# Pyro_Cut-Down.net
KiCad netlist of a schematic drawn in EAGLE
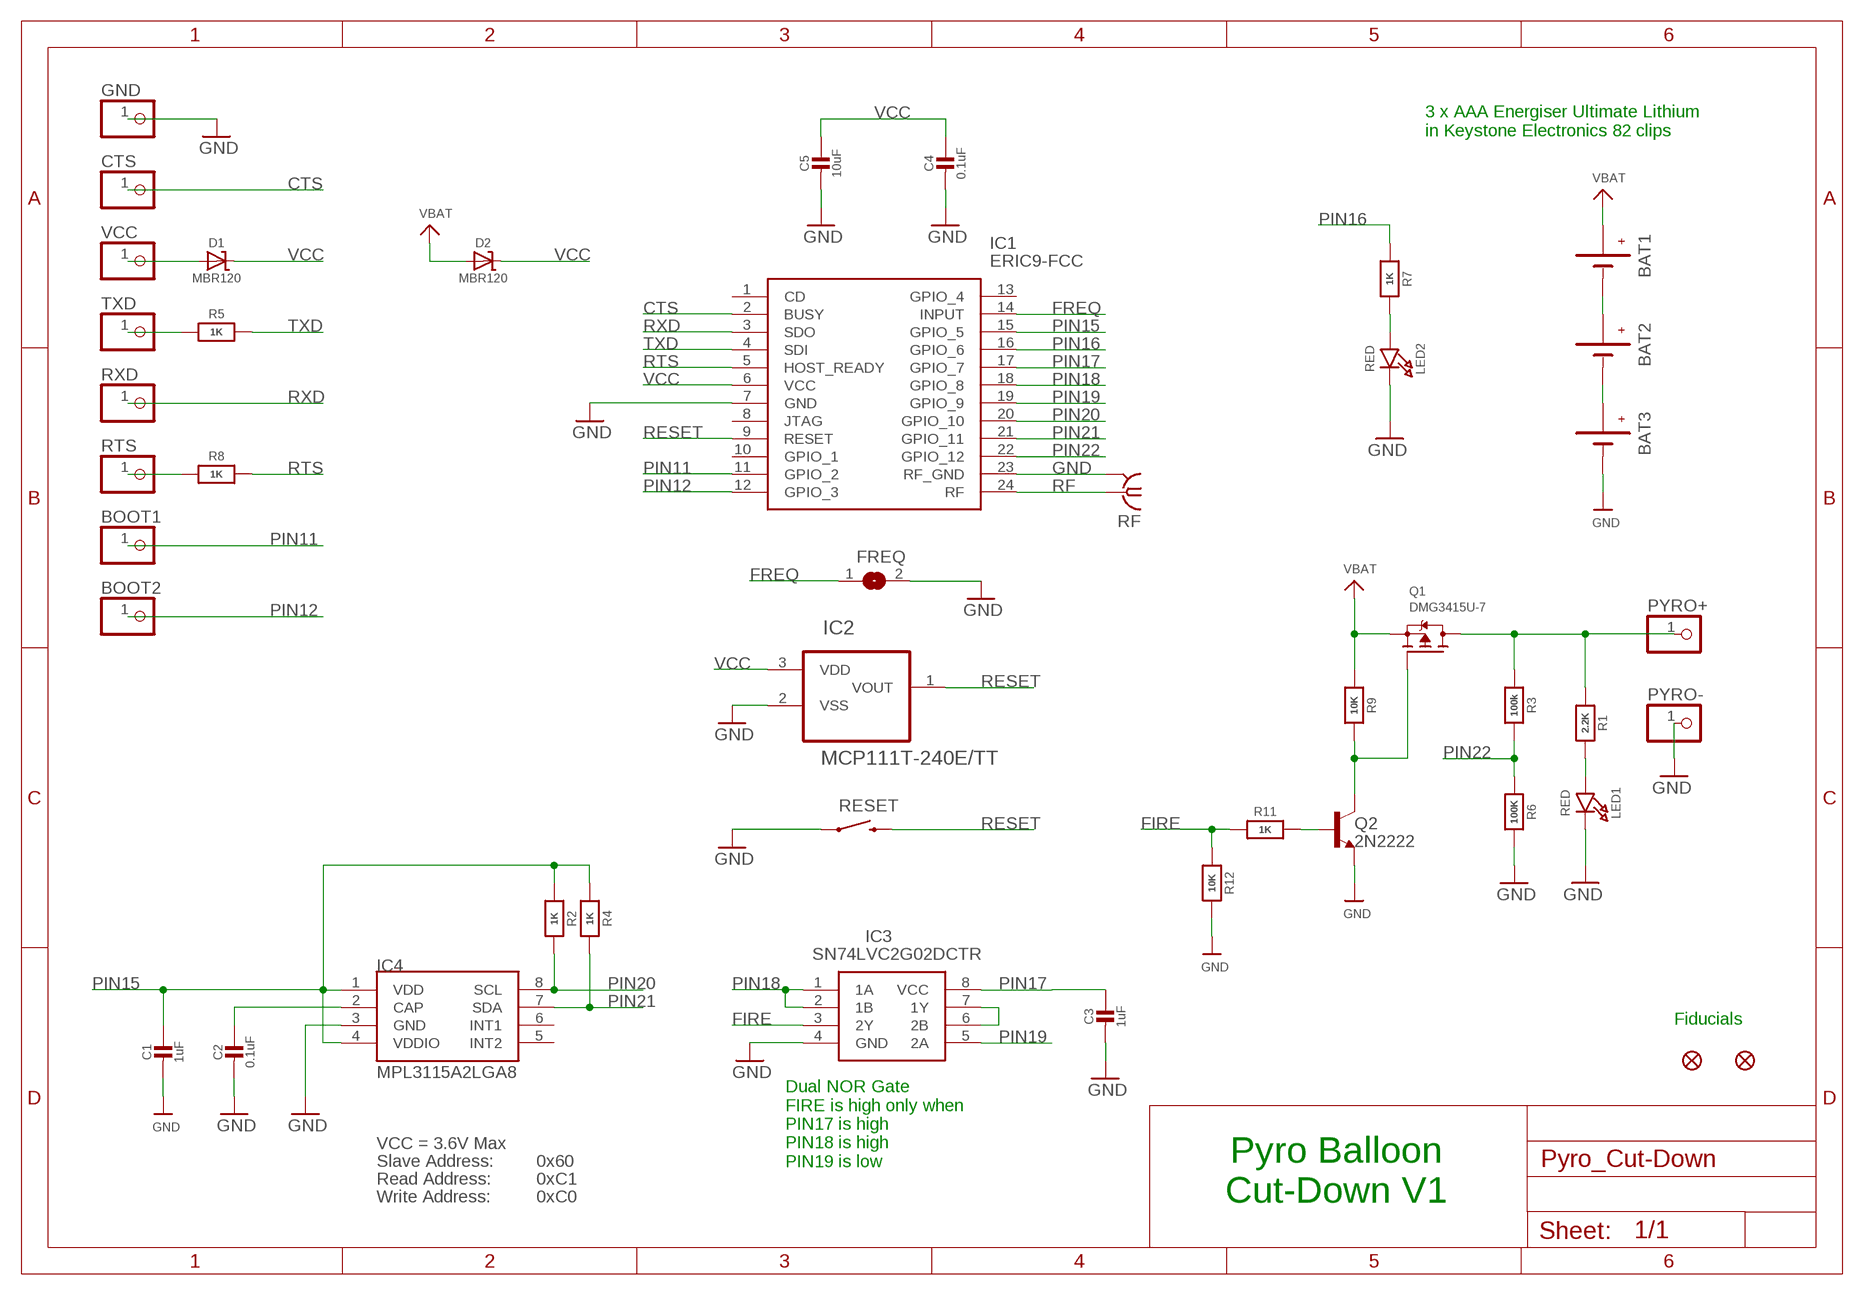
[diagram p0: schematic, sheet 1]

(export (version "E")
  (design (tool "Eeschema 10.0.6"))
  (components
    (comp (ref "BAT1")
      (value "BATTERYKEYSTONE82")
      (footprint "eagle-import:BATTERY-AAA-KEYSTONE82")
      (libsource (lib "eagle-import") (part "BATTERYKEYSTONE82"))
    )
    (comp (ref "BAT2")
      (value "BATTERYKEYSTONE82")
      (footprint "eagle-import:BATTERY-AAA-KEYSTONE82")
      (libsource (lib "eagle-import") (part "BATTERYKEYSTONE82"))
    )
    (comp (ref "BAT3")
      (value "BATTERYKEYSTONE82")
      (footprint "eagle-import:BATTERY-AAA-KEYSTONE82")
      (libsource (lib "eagle-import") (part "BATTERYKEYSTONE82"))
    )
    (comp (ref "BOOT1")
      (value "PINHD-1X1")
      (footprint "eagle-import:1X01")
      (libsource (lib "eagle-import") (part "PINHD-1X1"))
    )
    (comp (ref "BOOT2")
      (value "PINHD-1X1")
      (footprint "eagle-import:1X01")
      (libsource (lib "eagle-import") (part "PINHD-1X1"))
    )
    (comp (ref "C1")
      (value "1uF")
      (footprint "eagle-import:0603-NO")
      (libsource (lib "eagle-import") (part "CAP_CERAMIC0603_NO"))
    )
    (comp (ref "C2")
      (value "0.1uF")
      (footprint "eagle-import:0603-NO")
      (libsource (lib "eagle-import") (part "CAP_CERAMIC0603_NO"))
    )
    (comp (ref "C3")
      (value "1uF")
      (footprint "eagle-import:0603-NO")
      (libsource (lib "eagle-import") (part "CAP_CERAMIC0603_NO"))
    )
    (comp (ref "C4")
      (value "0.1uF")
      (footprint "eagle-import:0603-NO")
      (libsource (lib "eagle-import") (part "CAP_CERAMIC0603_NO"))
    )
    (comp (ref "C5")
      (value "10uF")
      (footprint "eagle-import:0805-NO")
      (libsource (lib "eagle-import") (part "CAP_CERAMIC0805-NOOUTLINE"))
    )
    (comp (ref "CTS")
      (value "PINHD-1X1")
      (footprint "eagle-import:1X01")
      (libsource (lib "eagle-import") (part "PINHD-1X1"))
    )
    (comp (ref "D1")
      (value "MBR120")
      (footprint "eagle-import:SOD-123")
      (libsource (lib "eagle-import") (part "DIODE-SCHOTTKYSOD-123"))
    )
    (comp (ref "D2")
      (value "MBR120")
      (footprint "eagle-import:SOD-123")
      (libsource (lib "eagle-import") (part "DIODE-SCHOTTKYSOD-123"))
    )
    (comp (ref "FD1")
      (value "FIDUCIAL1X2")
      (footprint "eagle-import:FIDUCIAL-1X2")
      (libsource (lib "eagle-import") (part "FIDUCIAL1X2"))
    )
    (comp (ref "FD2")
      (value "FIDUCIAL1X2")
      (footprint "eagle-import:FIDUCIAL-1X2")
      (libsource (lib "eagle-import") (part "FIDUCIAL1X2"))
    )
    (comp (ref "FREQ")
      (value "SOLDERJUMPER")
      (footprint "eagle-import:SOLDERJUMPER_ARROW_NOPASTE")
      (libsource (lib "eagle-import") (part "SOLDERJUMPER"))
    )
    (comp (ref "GND")
      (value "PINHD-1X1")
      (footprint "eagle-import:1X01")
      (libsource (lib "eagle-import") (part "PINHD-1X1"))
    )
    (comp (ref "IC1")
      (value "ERIC9-FCC")
      (footprint "eagle-import:ERIC4")
      (fields (field (name "ARROW_PART_NUMBER") "eRIC9-FCC"))
      (libsource (lib "eagle-import") (part "ERIC9-FCC"))
    )
    (comp (ref "IC2")
      (value "MCP111T-240E/TT")
      (footprint "eagle-import:SOT95P237X112-3N")
      (fields (field (name "MPN") "MCP111T-270E/TT") (field (name "MPN_1") "MCP111T-240E/TT"))
      (libsource (lib "eagle-import") (part "MCP111T-270E/TT"))
    )
    (comp (ref "IC3")
      (value "SN74LVC2G02DCTR")
      (footprint "eagle-import:SOP65P400X130-8N")
      (libsource (lib "eagle-import") (part "SN74LVC2G02DCTR"))
    )
    (comp (ref "IC4")
      (value "MPL3115A2LGA8")
      (footprint "eagle-import:LGA8")
      (libsource (lib "eagle-import") (part "MPL3115A2LGA8"))
    )
    (comp (ref "LED1")
      (value "RED")
      (footprint "eagle-import:CHIPLED_0805_NOOUTLINE")
      (libsource (lib "eagle-import") (part "LED0805_NOOUTLINE"))
    )
    (comp (ref "LED2")
      (value "RED")
      (footprint "eagle-import:CHIPLED_0805_NOOUTLINE")
      (libsource (lib "eagle-import") (part "LED0805_NOOUTLINE"))
    )
    (comp (ref "PYRO+")
      (value "PINHD-1X1")
      (footprint "eagle-import:1X01")
      (libsource (lib "eagle-import") (part "PINHD-1X1"))
    )
    (comp (ref "PYRO-")
      (value "PINHD-1X1")
      (footprint "eagle-import:1X01")
      (libsource (lib "eagle-import") (part "PINHD-1X1"))
    )
    (comp (ref "Q1")
      (value "DMG3415U-7")
      (footprint "eagle-import:SOT23-WIDE")
      (libsource (lib "eagle-import") (part "MOSFET-PWIDE"))
    )
    (comp (ref "Q2")
      (value "2N2222")
      (footprint "eagle-import:SOT23-BEC")
      (libsource (lib "eagle-import") (part "-NPN-SOT23-BECMMBT2222ALT1"))
    )
    (comp (ref "R1")
      (value "2.2K")
      (footprint "eagle-import:0603-NO")
      (libsource (lib "eagle-import") (part "RESISTOR_0603_NOOUT"))
    )
    (comp (ref "R2")
      (value "1K")
      (footprint "eagle-import:0603-NO")
      (libsource (lib "eagle-import") (part "RESISTOR_0603_NOOUT"))
    )
    (comp (ref "R3")
      (value "100k")
      (footprint "eagle-import:0603-NO")
      (libsource (lib "eagle-import") (part "RESISTOR_0603_NOOUT"))
    )
    (comp (ref "R4")
      (value "1K")
      (footprint "eagle-import:0603-NO")
      (libsource (lib "eagle-import") (part "RESISTOR_0603_NOOUT"))
    )
    (comp (ref "R5")
      (value "1K")
      (footprint "eagle-import:0603-NO")
      (libsource (lib "eagle-import") (part "RESISTOR_0603_NOOUT"))
    )
    (comp (ref "R6")
      (value "100K")
      (footprint "eagle-import:0603-NO")
      (libsource (lib "eagle-import") (part "RESISTOR_0603_NOOUT"))
    )
    (comp (ref "R7")
      (value "1K")
      (footprint "eagle-import:0603-NO")
      (libsource (lib "eagle-import") (part "RESISTOR_0603_NOOUT"))
    )
    (comp (ref "R8")
      (value "1K")
      (footprint "eagle-import:0603-NO")
      (libsource (lib "eagle-import") (part "RESISTOR_0603_NOOUT"))
    )
    (comp (ref "R9")
      (value "10K")
      (footprint "eagle-import:0603-NO")
      (libsource (lib "eagle-import") (part "RESISTOR_0603_NOOUT"))
    )
    (comp (ref "R11")
      (value "1K")
      (footprint "eagle-import:0603-NO")
      (libsource (lib "eagle-import") (part "RESISTOR_0603_NOOUT"))
    )
    (comp (ref "R12")
      (value "10K")
      (footprint "eagle-import:0603-NO")
      (libsource (lib "eagle-import") (part "RESISTOR_0603_NOOUT"))
    )
    (comp (ref "RESET")
      (value "SWITCH-MOMENTARY-2PTH")
      (footprint "eagle-import:TACTILE-PTH")
      (libsource (lib "eagle-import") (part "SWITCH-MOMENTARY-2PTH"))
    )
    (comp (ref "RF")
      (value "SMA-142-0711-821/826")
      (footprint "eagle-import:J502-ND-142-0711-821_826")
      (fields (field (name "MF") "JOHNSON COMPONENTS") (field (name "MPN") "142-0711-821"))
      (libsource (lib "eagle-import") (part "SMA-142-0711-821/826"))
    )
    (comp (ref "RTS")
      (value "PINHD-1X1")
      (footprint "eagle-import:1X01")
      (libsource (lib "eagle-import") (part "PINHD-1X1"))
    )
    (comp (ref "RXD")
      (value "PINHD-1X1")
      (footprint "eagle-import:1X01")
      (libsource (lib "eagle-import") (part "PINHD-1X1"))
    )
    (comp (ref "TXD")
      (value "PINHD-1X1")
      (footprint "eagle-import:1X01")
      (libsource (lib "eagle-import") (part "PINHD-1X1"))
    )
    (comp (ref "VCC")
      (value "PINHD-1X1")
      (footprint "eagle-import:1X01")
      (libsource (lib "eagle-import") (part "PINHD-1X1"))
    )
  )
  (nets
    (net (code "1") (name "/CTS") (class "Default")
      (node (ref "CTS") (pin "1") (pinfunction "1_1") (pintype "passive"))
      (node (ref "IC1") (pin "2") (pinfunction "BUSY_2") (pintype "bidirectional"))
    )
    (net (code "2") (name "/FIRE") (class "Default")
      (node (ref "IC3") (pin "3") (pinfunction "2Y_3") (pintype "bidirectional"))
      (node (ref "R11") (pin "1") (pinfunction "1_1") (pintype "passive"))
      (node (ref "R12") (pin "1") (pinfunction "1_1") (pintype "passive"))
    )
    (net (code "3") (name "/FREQ") (class "Default")
      (node (ref "FREQ") (pin "1") (pinfunction "1_1") (pintype "passive"))
      (node (ref "IC1") (pin "14") (pinfunction "INPUT_14") (pintype "bidirectional"))
    )
    (net (code "4") (name "/PIN11") (class "Default")
      (node (ref "BOOT1") (pin "1") (pinfunction "1_1") (pintype "passive"))
      (node (ref "IC1") (pin "11") (pinfunction "GPIO_2_11") (pintype "bidirectional"))
    )
    (net (code "5") (name "/PIN12") (class "Default")
      (node (ref "BOOT2") (pin "1") (pinfunction "1_1") (pintype "passive"))
      (node (ref "IC1") (pin "12") (pinfunction "GPIO_3_12") (pintype "bidirectional"))
    )
    (net (code "6") (name "/PIN15") (class "Default")
      (node (ref "C1") (pin "1") (pinfunction "1_1") (pintype "passive"))
      (node (ref "IC1") (pin "15") (pinfunction "GPIO_5_15") (pintype "bidirectional"))
      (node (ref "IC4") (pin "1") (pinfunction "VDD_1") (pintype "bidirectional"))
      (node (ref "IC4") (pin "4") (pinfunction "VDDIO_4") (pintype "bidirectional"))
      (node (ref "R2") (pin "1") (pinfunction "1_1") (pintype "passive"))
      (node (ref "R4") (pin "1") (pinfunction "1_1") (pintype "passive"))
    )
    (net (code "7") (name "/PIN16") (class "Default")
      (node (ref "IC1") (pin "16") (pinfunction "GPIO_6_16") (pintype "bidirectional"))
      (node (ref "R7") (pin "1") (pinfunction "1_1") (pintype "passive"))
    )
    (net (code "8") (name "/PIN17") (class "Default")
      (node (ref "C3") (pin "1") (pinfunction "1_1") (pintype "passive"))
      (node (ref "IC1") (pin "17") (pinfunction "GPIO_7_17") (pintype "bidirectional"))
      (node (ref "IC3") (pin "8") (pinfunction "VCC_8") (pintype "bidirectional"))
    )
    (net (code "9") (name "/PIN18") (class "Default")
      (node (ref "IC1") (pin "18") (pinfunction "GPIO_8_18") (pintype "bidirectional"))
      (node (ref "IC3") (pin "1") (pinfunction "1A_1") (pintype "bidirectional"))
      (node (ref "IC3") (pin "2") (pinfunction "1B_2") (pintype "bidirectional"))
    )
    (net (code "10") (name "/PIN19") (class "Default")
      (node (ref "IC1") (pin "19") (pinfunction "GPIO_9_19") (pintype "bidirectional"))
      (node (ref "IC3") (pin "5") (pinfunction "2A_5") (pintype "bidirectional"))
    )
    (net (code "11") (name "/PIN20") (class "Default")
      (node (ref "IC1") (pin "20") (pinfunction "GPIO_10_20") (pintype "bidirectional"))
      (node (ref "IC4") (pin "8") (pinfunction "SCL_8") (pintype "bidirectional"))
      (node (ref "R2") (pin "2") (pinfunction "2_2") (pintype "passive"))
    )
    (net (code "12") (name "/PIN21") (class "Default")
      (node (ref "IC1") (pin "21") (pinfunction "GPIO_11_21") (pintype "bidirectional"))
      (node (ref "IC4") (pin "7") (pinfunction "SDA_7") (pintype "bidirectional"))
      (node (ref "R4") (pin "2") (pinfunction "2_2") (pintype "passive"))
    )
    (net (code "13") (name "/PIN22") (class "Default")
      (node (ref "IC1") (pin "22") (pinfunction "GPIO_12_22") (pintype "bidirectional"))
      (node (ref "R3") (pin "2") (pinfunction "2_2") (pintype "passive"))
      (node (ref "R6") (pin "1") (pinfunction "1_1") (pintype "passive"))
    )
    (net (code "14") (name "/RESET") (class "Default")
      (node (ref "IC1") (pin "9") (pinfunction "RESET_9") (pintype "bidirectional"))
      (node (ref "IC2") (pin "1") (pinfunction "VOUT_1") (pintype "output"))
      (node (ref "RESET") (pin "3") (pinfunction "2_3") (pintype "passive"))
    )
    (net (code "15") (name "/RF") (class "Default")
      (node (ref "IC1") (pin "24") (pinfunction "RF_24") (pintype "bidirectional"))
      (node (ref "RF") (pin "1") (pinfunction "1_1") (pintype "passive"))
    )
    (net (code "16") (name "/RTS") (class "Default")
      (node (ref "IC1") (pin "5") (pinfunction "HOST_READY_5") (pintype "bidirectional"))
      (node (ref "R8") (pin "2") (pinfunction "2_2") (pintype "passive"))
    )
    (net (code "17") (name "/RXD") (class "Default")
      (node (ref "IC1") (pin "3") (pinfunction "SDO_3") (pintype "bidirectional"))
      (node (ref "RXD") (pin "1") (pinfunction "1_1") (pintype "passive"))
    )
    (net (code "18") (name "/TXD") (class "Default")
      (node (ref "IC1") (pin "4") (pinfunction "SDI_4") (pintype "bidirectional"))
      (node (ref "R5") (pin "2") (pinfunction "2_2") (pintype "passive"))
    )
    (net (code "19") (name "/VCC") (class "Default")
      (node (ref "C4") (pin "1") (pinfunction "1_1") (pintype "passive"))
      (node (ref "C5") (pin "1") (pinfunction "1_1") (pintype "passive"))
      (node (ref "D1") (pin "C") (pinfunction "C_C") (pintype "passive"))
      (node (ref "D2") (pin "C") (pinfunction "C_C") (pintype "passive"))
      (node (ref "IC1") (pin "6") (pinfunction "VCC_6") (pintype "bidirectional"))
      (node (ref "IC2") (pin "3") (pinfunction "VDD_3") (pintype "power_in"))
    )
    (net (code "20") (name "GND") (class "Default")
      (node (ref "BAT3") (pin "GND@1") (pinfunction "-_GND@1") (pintype "power_in"))
      (node (ref "BAT3") (pin "GND@2") (pinfunction "-_GND@2") (pintype "power_in"))
      (node (ref "C1") (pin "2") (pinfunction "2_2") (pintype "passive"))
      (node (ref "C2") (pin "2") (pinfunction "2_2") (pintype "passive"))
      (node (ref "C3") (pin "2") (pinfunction "2_2") (pintype "passive"))
      (node (ref "C4") (pin "2") (pinfunction "2_2") (pintype "passive"))
      (node (ref "C5") (pin "2") (pinfunction "2_2") (pintype "passive"))
      (node (ref "FREQ") (pin "2") (pinfunction "2_2") (pintype "passive"))
      (node (ref "GND") (pin "1") (pinfunction "1_1") (pintype "passive"))
      (node (ref "IC1") (pin "23") (pinfunction "RF_GND_23") (pintype "bidirectional"))
      (node (ref "IC1") (pin "7") (pinfunction "GND_7") (pintype "bidirectional"))
      (node (ref "IC2") (pin "2") (pinfunction "VSS_2") (pintype "power_in"))
      (node (ref "IC3") (pin "4") (pinfunction "GND_4") (pintype "bidirectional"))
      (node (ref "IC4") (pin "3") (pinfunction "GND_3") (pintype "bidirectional"))
      (node (ref "LED1") (pin "C") (pinfunction "C_C") (pintype "passive"))
      (node (ref "LED2") (pin "C") (pinfunction "C_C") (pintype "passive"))
      (node (ref "PYRO-") (pin "1") (pinfunction "1_1") (pintype "passive"))
      (node (ref "Q2") (pin "E") (pinfunction "E_E") (pintype "passive"))
      (node (ref "R12") (pin "2") (pinfunction "2_2") (pintype "passive"))
      (node (ref "R6") (pin "2") (pinfunction "2_2") (pintype "passive"))
      (node (ref "RESET") (pin "1") (pinfunction "1_1") (pintype "passive"))
      (node (ref "RF") (pin "G@1") (pinfunction "2_G@1") (pintype "passive"))
      (node (ref "RF") (pin "G@2") (pinfunction "2_G@2") (pintype "passive"))
      (node (ref "RF") (pin "G@3") (pinfunction "2_G@3") (pintype "passive"))
      (node (ref "RF") (pin "G@4") (pinfunction "2_G@4") (pintype "passive"))
    )
    (net (code "21") (name "Net-(BAT1---PadGND@1)") (class "Default")
      (node (ref "BAT1") (pin "GND@1") (pinfunction "-_GND@1") (pintype "power_in"))
      (node (ref "BAT1") (pin "GND@2") (pinfunction "-_GND@2") (pintype "power_in"))
      (node (ref "BAT2") (pin "PWR@1") (pinfunction "+_PWR@1") (pintype "power_in"))
      (node (ref "BAT2") (pin "PWR@2") (pinfunction "+_PWR@2") (pintype "power_in"))
    )
    (net (code "22") (name "Net-(BAT2---PadGND@1)") (class "Default")
      (node (ref "BAT2") (pin "GND@1") (pinfunction "-_GND@1") (pintype "power_in"))
      (node (ref "BAT2") (pin "GND@2") (pinfunction "-_GND@2") (pintype "power_in"))
      (node (ref "BAT3") (pin "PWR@1") (pinfunction "+_PWR@1") (pintype "power_in"))
      (node (ref "BAT3") (pin "PWR@2") (pinfunction "+_PWR@2") (pintype "power_in"))
    )
    (net (code "23") (name "Net-(D1-PadA)") (class "Default")
      (node (ref "D1") (pin "A") (pinfunction "A_A") (pintype "passive"))
      (node (ref "VCC") (pin "1") (pinfunction "1_1") (pintype "passive"))
    )
    (net (code "24") (name "Net-(IC3-1Y)") (class "Default")
      (node (ref "IC3") (pin "6") (pinfunction "2B_6") (pintype "bidirectional"))
      (node (ref "IC3") (pin "7") (pinfunction "1Y_7") (pintype "bidirectional"))
    )
    (net (code "25") (name "Net-(IC4-CAP)") (class "Default")
      (node (ref "C2") (pin "1") (pinfunction "1_1") (pintype "passive"))
      (node (ref "IC4") (pin "2") (pinfunction "CAP_2") (pintype "bidirectional"))
    )
    (net (code "26") (name "Net-(LED1-PadA)") (class "Default")
      (node (ref "LED1") (pin "A") (pinfunction "A_A") (pintype "passive"))
      (node (ref "R1") (pin "2") (pinfunction "2_2") (pintype "passive"))
    )
    (net (code "27") (name "Net-(LED2-PadA)") (class "Default")
      (node (ref "LED2") (pin "A") (pinfunction "A_A") (pintype "passive"))
      (node (ref "R7") (pin "2") (pinfunction "2_2") (pintype "passive"))
    )
    (net (code "28") (name "Net-(Q1-D)") (class "Default")
      (node (ref "PYRO+") (pin "1") (pinfunction "1_1") (pintype "passive"))
      (node (ref "Q1") (pin "3") (pinfunction "D_3") (pintype "passive"))
      (node (ref "R1") (pin "1") (pinfunction "1_1") (pintype "passive"))
      (node (ref "R3") (pin "1") (pinfunction "1_1") (pintype "passive"))
    )
    (net (code "29") (name "Net-(Q1-G)") (class "Default")
      (node (ref "Q1") (pin "1") (pinfunction "G_1") (pintype "passive"))
      (node (ref "Q2") (pin "C") (pinfunction "C_C") (pintype "passive"))
      (node (ref "R9") (pin "2") (pinfunction "2_2") (pintype "passive"))
    )
    (net (code "30") (name "Net-(Q2-PadB)") (class "Default")
      (node (ref "Q2") (pin "B") (pinfunction "B_B") (pintype "passive"))
      (node (ref "R11") (pin "2") (pinfunction "2_2") (pintype "passive"))
    )
    (net (code "31") (name "Net-(R5-Pad1)") (class "Default")
      (node (ref "R5") (pin "1") (pinfunction "1_1") (pintype "passive"))
      (node (ref "TXD") (pin "1") (pinfunction "1_1") (pintype "passive"))
    )
    (net (code "32") (name "Net-(R8-Pad1)") (class "Default")
      (node (ref "R8") (pin "1") (pinfunction "1_1") (pintype "passive"))
      (node (ref "RTS") (pin "1") (pinfunction "1_1") (pintype "passive"))
    )
    (net (code "33") (name "VBAT") (class "Default")
      (node (ref "BAT1") (pin "PWR@1") (pinfunction "+_PWR@1") (pintype "power_in"))
      (node (ref "BAT1") (pin "PWR@2") (pinfunction "+_PWR@2") (pintype "power_in"))
      (node (ref "D2") (pin "A") (pinfunction "A_A") (pintype "passive"))
      (node (ref "Q1") (pin "2") (pinfunction "S_2") (pintype "passive"))
      (node (ref "R9") (pin "1") (pinfunction "1_1") (pintype "passive"))
    )
    (net (code "34") (name "unconnected-(IC1-CD-Pad1)") (class "Default")
      (node (ref "IC1") (pin "1") (pinfunction "CD_1") (pintype "bidirectional"))
    )
    (net (code "35") (name "unconnected-(IC1-GPIO_1-Pad10)") (class "Default")
      (node (ref "IC1") (pin "10") (pinfunction "GPIO_1_10") (pintype "bidirectional"))
    )
    (net (code "36") (name "unconnected-(IC1-GPIO_4-Pad13)") (class "Default")
      (node (ref "IC1") (pin "13") (pinfunction "GPIO_4_13") (pintype "bidirectional"))
    )
    (net (code "37") (name "unconnected-(IC1-JTAG-Pad8)") (class "Default")
      (node (ref "IC1") (pin "8") (pinfunction "JTAG_8") (pintype "bidirectional"))
    )
    (net (code "38") (name "unconnected-(IC4-INT1-Pad6)") (class "Default")
      (node (ref "IC4") (pin "6") (pinfunction "INT1_6") (pintype "bidirectional"))
    )
    (net (code "39") (name "unconnected-(IC4-INT2-Pad5)") (class "Default")
      (node (ref "IC4") (pin "5") (pinfunction "INT2_5") (pintype "bidirectional"))
    )
  )
)
